# INSIDER.net
KiCad netlist of a schematic drawn in EAGLE
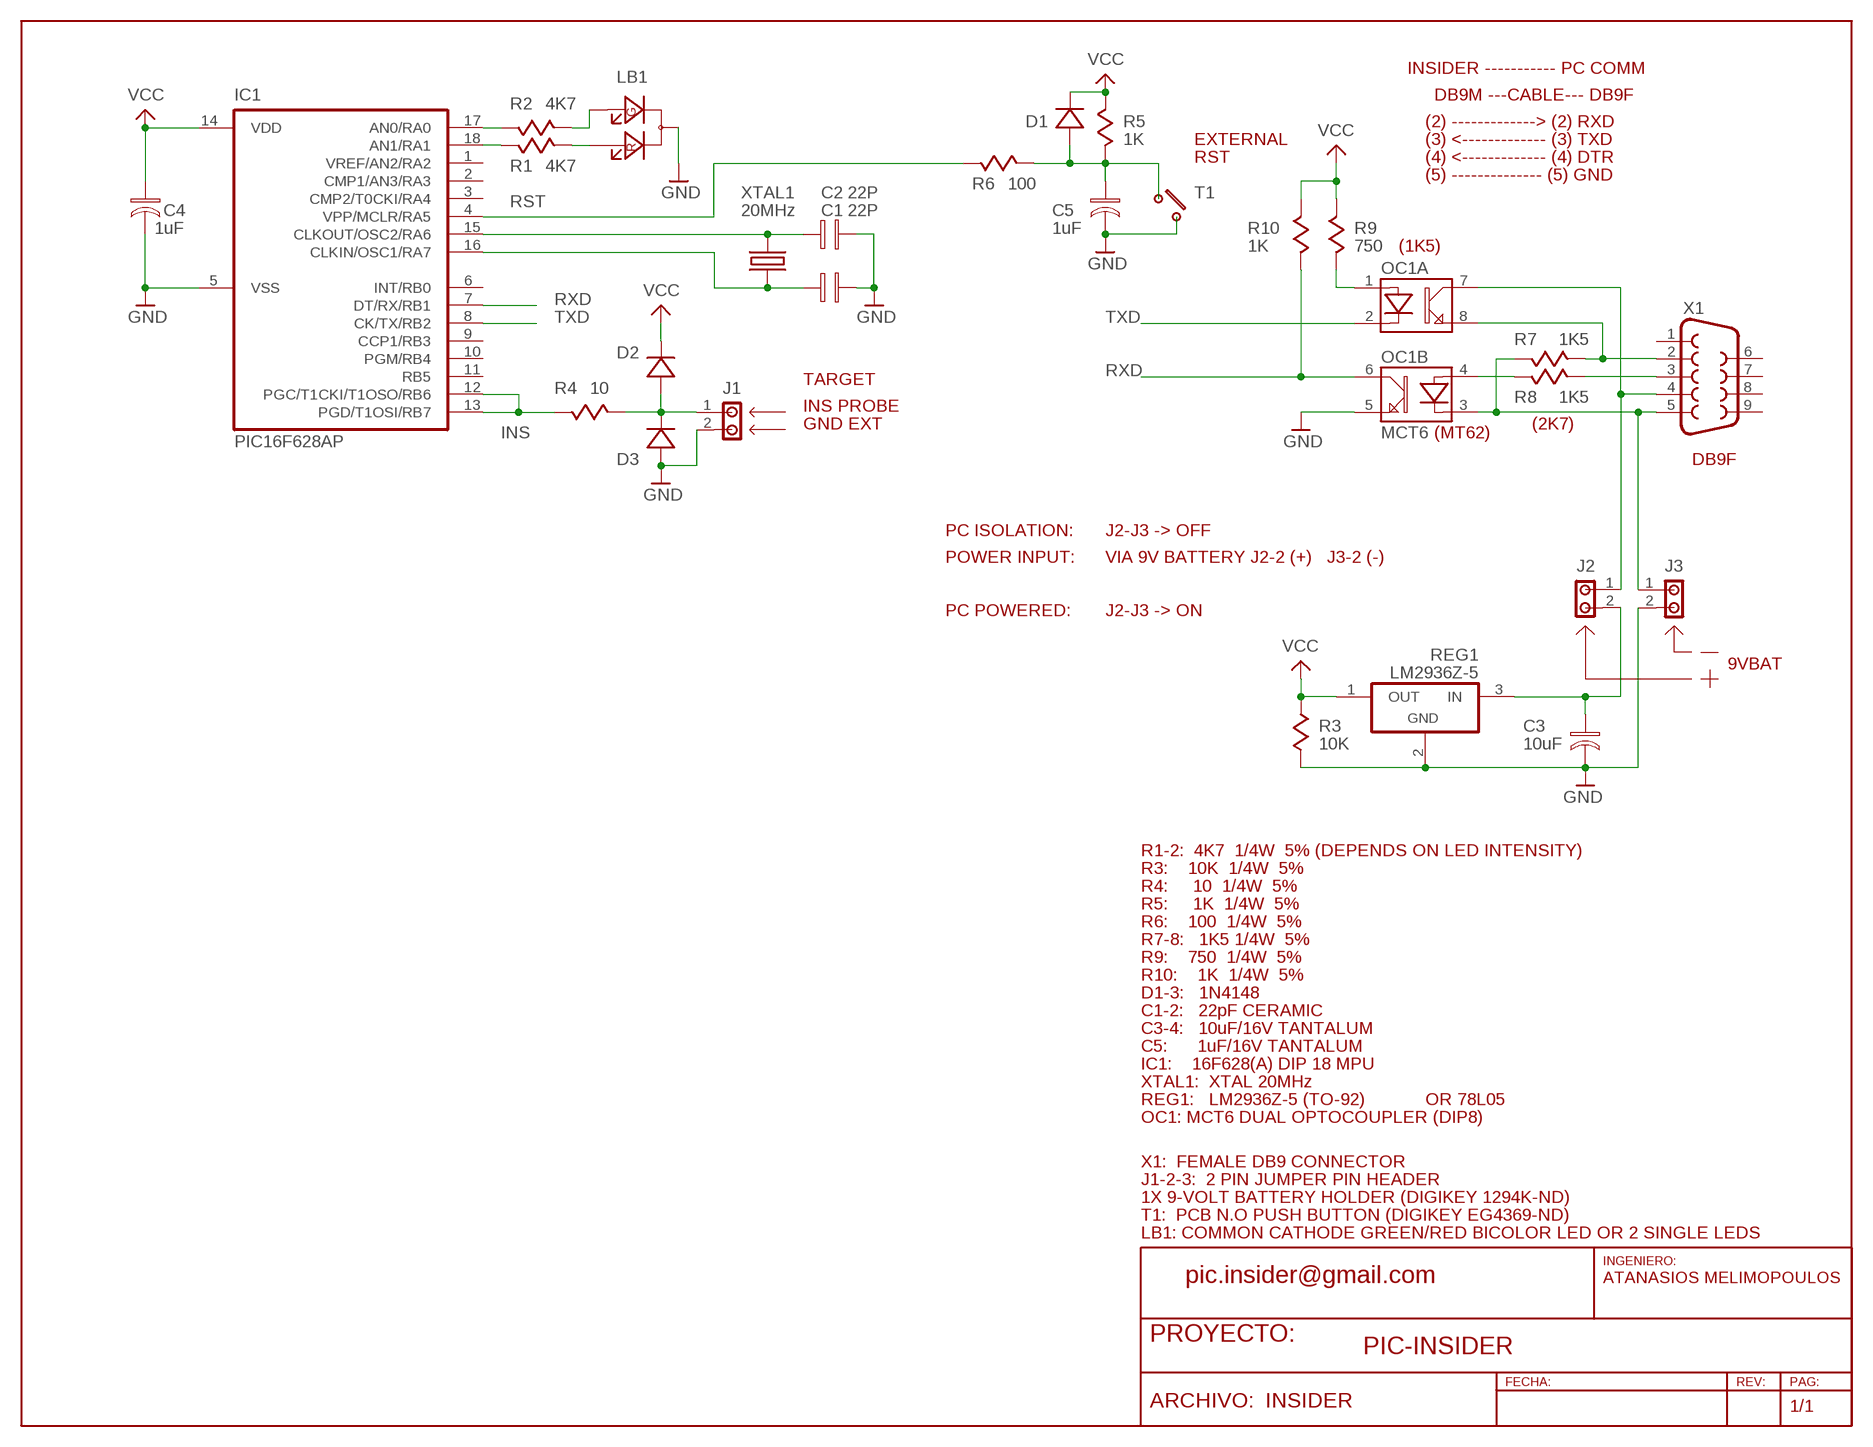
[diagram p0: schematic, sheet 1]

(export (version "E")
  (design (tool "Eeschema 10.0.6"))
  (components
    (comp (ref "C1")
      (value "22P")
      (footprint "eagle-import:C02")
      (libsource (lib "eagle-import") (part "CAP02"))
    )
    (comp (ref "C2")
      (value "22P")
      (footprint "eagle-import:C02")
      (libsource (lib "eagle-import") (part "CAP02"))
    )
    (comp (ref "C3")
      (value "10uF")
      (footprint "eagle-import:CP01")
      (libsource (lib "eagle-import") (part "CAPE01"))
    )
    (comp (ref "C4")
      (value "1uF")
      (footprint "eagle-import:CP01")
      (libsource (lib "eagle-import") (part "CAPE01"))
    )
    (comp (ref "C5")
      (value "1uF")
      (footprint "eagle-import:CP01")
      (libsource (lib "eagle-import") (part "CAPE01"))
    )
    (comp (ref "D1")
      (value "1N4148")
      (footprint "eagle-import:D03")
      (libsource (lib "eagle-import") (part "DIODE03"))
    )
    (comp (ref "D2")
      (value "1N4148")
      (footprint "eagle-import:D03")
      (libsource (lib "eagle-import") (part "DIODE03"))
    )
    (comp (ref "D3")
      (value "1N4148")
      (footprint "eagle-import:D03")
      (libsource (lib "eagle-import") (part "DIODE03"))
    )
    (comp (ref "IC1")
      (value "PIC16F628AP")
      (footprint "eagle-import:DIL18")
      (libsource (lib "eagle-import") (part "PIC16F6P28A"))
    )
    (comp (ref "J1")
      (value "JMP2")
      (footprint "eagle-import:JP2")
      (libsource (lib "eagle-import") (part "JMP2"))
    )
    (comp (ref "J2")
      (value "JMP2")
      (footprint "eagle-import:JP2")
      (libsource (lib "eagle-import") (part "JMP2"))
    )
    (comp (ref "J3")
      (value "JMP2")
      (footprint "eagle-import:JP2")
      (libsource (lib "eagle-import") (part "JMP2"))
    )
    (comp (ref "LB1")
      (value "LEDBIKC")
      (footprint "eagle-import:LEDBKC")
      (libsource (lib "eagle-import") (part "LEDBIKC"))
    )
    (comp (ref "OC1")
      (value "MCT6")
      (footprint "eagle-import:DIL08")
      (libsource (lib "eagle-import") (part "OPTO2G"))
    )
    (comp (ref "R1")
      (value "4K7")
      (footprint "eagle-import:R03")
      (libsource (lib "eagle-import") (part "RES03"))
    )
    (comp (ref "R2")
      (value "4K7")
      (footprint "eagle-import:R03")
      (libsource (lib "eagle-import") (part "RES03"))
    )
    (comp (ref "R3")
      (value "10K")
      (footprint "eagle-import:R03")
      (libsource (lib "eagle-import") (part "RES03"))
    )
    (comp (ref "R4")
      (value "10")
      (footprint "eagle-import:R03")
      (libsource (lib "eagle-import") (part "RES03"))
    )
    (comp (ref "R5")
      (value "1K")
      (footprint "eagle-import:R03")
      (libsource (lib "eagle-import") (part "RES03"))
    )
    (comp (ref "R6")
      (value "100")
      (footprint "eagle-import:R03")
      (libsource (lib "eagle-import") (part "RES03"))
    )
    (comp (ref "R7")
      (value "1K5")
      (footprint "eagle-import:R03")
      (libsource (lib "eagle-import") (part "RES03"))
    )
    (comp (ref "R8")
      (value "1K5")
      (footprint "eagle-import:R03")
      (libsource (lib "eagle-import") (part "RES03"))
    )
    (comp (ref "R9")
      (value "750")
      (footprint "eagle-import:R03")
      (libsource (lib "eagle-import") (part "RES03"))
    )
    (comp (ref "R10")
      (value "1K")
      (footprint "eagle-import:R03")
      (libsource (lib "eagle-import") (part "RES03"))
    )
    (comp (ref "REG1")
      (value "LM2936Z-5")
      (footprint "eagle-import:TO92A")
      (libsource (lib "eagle-import") (part "78XXL"))
    )
    (comp (ref "T1")
      (value "TEC3")
      (footprint "eagle-import:TEC3L")
      (libsource (lib "eagle-import") (part "TEC3"))
    )
    (comp (ref "X1")
      (value "F09D")
      (footprint "eagle-import:F09D")
      (libsource (lib "eagle-import") (part "F09D"))
    )
    (comp (ref "XTAL1")
      (value "20MHz")
      (footprint "eagle-import:HC49V")
      (libsource (lib "eagle-import") (part "XTALV300"))
    )
  )
  (nets
    (net (code "1") (name "/INS") (class "Default")
      (node (ref "IC1") (pin "12") (pinfunction "PGC/T1CKI/T1OSO/RB6_12") (pintype "bidirectional"))
      (node (ref "IC1") (pin "13") (pinfunction "PGD/T1OSI/RB7_13") (pintype "bidirectional"))
      (node (ref "R4") (pin "P$1") (pinfunction "1_P$1") (pintype "passive"))
    )
    (net (code "2") (name "/RST") (class "Default")
      (node (ref "IC1") (pin "4") (pinfunction "VPP/MCLR/RA5_4") (pintype "input"))
      (node (ref "R6") (pin "P$1") (pinfunction "1_P$1") (pintype "passive"))
    )
    (net (code "3") (name "/RXD") (class "Default")
      (node (ref "IC1") (pin "7") (pinfunction "DT/RX/RB1_7") (pintype "bidirectional"))
      (node (ref "OC1") (pin "6") (pinfunction "C_6") (pintype "passive"))
      (node (ref "R10") (pin "P$1") (pinfunction "1_P$1") (pintype "passive"))
    )
    (net (code "4") (name "/TXD") (class "Default")
      (node (ref "IC1") (pin "8") (pinfunction "CK/TX/RB2_8") (pintype "bidirectional"))
      (node (ref "OC1") (pin "2") (pinfunction "K_2") (pintype "passive"))
    )
    (net (code "5") (name "GND") (class "Default")
      (node (ref "C1") (pin "P$2") (pinfunction "2_P$2") (pintype "passive"))
      (node (ref "C2") (pin "P$2") (pinfunction "2_P$2") (pintype "passive"))
      (node (ref "C3") (pin "P$2") (pinfunction "2_P$2") (pintype "passive"))
      (node (ref "C4") (pin "P$2") (pinfunction "2_P$2") (pintype "passive"))
      (node (ref "C5") (pin "P$2") (pinfunction "2_P$2") (pintype "passive"))
      (node (ref "D3") (pin "P$1") (pinfunction "A_P$1") (pintype "passive"))
      (node (ref "IC1") (pin "5") (pinfunction "VSS_5") (pintype "power_in"))
      (node (ref "J1") (pin "2") (pinfunction "P$2_2") (pintype "bidirectional"))
      (node (ref "J3") (pin "2") (pinfunction "P$2_2") (pintype "bidirectional"))
      (node (ref "LB1") (pin "K") (pinfunction "K_K") (pintype "passive"))
      (node (ref "OC1") (pin "5") (pinfunction "E_5") (pintype "passive"))
      (node (ref "R3") (pin "P$2") (pinfunction "2_P$2") (pintype "passive"))
      (node (ref "REG1") (pin "2") (pinfunction "GND_2") (pintype "input"))
      (node (ref "T1") (pin "4") (pinfunction "P$2_4") (pintype "passive"))
    )
    (net (code "6") (name "Net-(C1-1)") (class "Default")
      (node (ref "C1") (pin "P$1") (pinfunction "1_P$1") (pintype "passive"))
      (node (ref "IC1") (pin "16") (pinfunction "CLKIN/OSC1/RA7_16") (pintype "bidirectional"))
      (node (ref "XTAL1") (pin "2") (pinfunction "P$2_2") (pintype "passive"))
    )
    (net (code "7") (name "Net-(C2-1)") (class "Default")
      (node (ref "C2") (pin "P$1") (pinfunction "1_P$1") (pintype "passive"))
      (node (ref "IC1") (pin "15") (pinfunction "CLKOUT/OSC2/RA6_15") (pintype "bidirectional"))
      (node (ref "XTAL1") (pin "1") (pinfunction "P$1_1") (pintype "passive"))
    )
    (net (code "8") (name "Net-(C3-1)") (class "Default")
      (node (ref "C3") (pin "P$1") (pinfunction "1_P$1") (pintype "passive"))
      (node (ref "J2") (pin "2") (pinfunction "P$2_2") (pintype "bidirectional"))
      (node (ref "REG1") (pin "3") (pinfunction "IN_3") (pintype "input"))
    )
    (net (code "9") (name "Net-(C5-1)") (class "Default")
      (node (ref "C5") (pin "P$1") (pinfunction "1_P$1") (pintype "passive"))
      (node (ref "D1") (pin "P$1") (pinfunction "A_P$1") (pintype "passive"))
      (node (ref "R5") (pin "P$2") (pinfunction "2_P$2") (pintype "passive"))
      (node (ref "R6") (pin "P$2") (pinfunction "2_P$2") (pintype "passive"))
      (node (ref "T1") (pin "1") (pinfunction "P$1_1") (pintype "passive"))
    )
    (net (code "10") (name "Net-(D2-A)") (class "Default")
      (node (ref "D2") (pin "P$1") (pinfunction "A_P$1") (pintype "passive"))
      (node (ref "D3") (pin "P$2") (pinfunction "K_P$2") (pintype "passive"))
      (node (ref "J1") (pin "1") (pinfunction "P$1_1") (pintype "bidirectional"))
      (node (ref "R4") (pin "P$2") (pinfunction "2_P$2") (pintype "passive"))
    )
    (net (code "11") (name "Net-(IC1-AN0{slash}RA0)") (class "Default")
      (node (ref "IC1") (pin "17") (pinfunction "AN0/RA0_17") (pintype "bidirectional"))
      (node (ref "R2") (pin "P$2") (pinfunction "2_P$2") (pintype "passive"))
    )
    (net (code "12") (name "Net-(IC1-AN1{slash}RA1)") (class "Default")
      (node (ref "IC1") (pin "18") (pinfunction "AN1/RA1_18") (pintype "bidirectional"))
      (node (ref "R1") (pin "P$2") (pinfunction "2_P$2") (pintype "passive"))
    )
    (net (code "13") (name "Net-(J2-P$1)") (class "Default")
      (node (ref "J2") (pin "1") (pinfunction "P$1_1") (pintype "bidirectional"))
      (node (ref "OC1") (pin "7") (pinfunction "C_7") (pintype "passive"))
      (node (ref "X1") (pin "4") (pinfunction "4_4") (pintype "passive"))
    )
    (net (code "14") (name "Net-(J3-P$1)") (class "Default")
      (node (ref "J3") (pin "1") (pinfunction "P$1_1") (pintype "bidirectional"))
      (node (ref "OC1") (pin "3") (pinfunction "K_3") (pintype "passive"))
      (node (ref "R7") (pin "P$2") (pinfunction "2_P$2") (pintype "passive"))
      (node (ref "X1") (pin "5") (pinfunction "5_5") (pintype "passive"))
    )
    (net (code "15") (name "Net-(LB1-A1)") (class "Default")
      (node (ref "LB1") (pin "R") (pinfunction "A1_R") (pintype "passive"))
      (node (ref "R1") (pin "P$1") (pinfunction "1_P$1") (pintype "passive"))
    )
    (net (code "16") (name "Net-(LB1-A2)") (class "Default")
      (node (ref "LB1") (pin "G") (pinfunction "A2_G") (pintype "passive"))
      (node (ref "R2") (pin "P$1") (pinfunction "1_P$1") (pintype "passive"))
    )
    (net (code "17") (name "Net-(OC1A-A)") (class "Default")
      (node (ref "OC1") (pin "1") (pinfunction "A_1") (pintype "passive"))
      (node (ref "R9") (pin "P$1") (pinfunction "1_P$1") (pintype "passive"))
    )
    (net (code "18") (name "Net-(OC1A-E)") (class "Default")
      (node (ref "OC1") (pin "8") (pinfunction "E_8") (pintype "passive"))
      (node (ref "R7") (pin "P$1") (pinfunction "1_P$1") (pintype "passive"))
      (node (ref "X1") (pin "2") (pinfunction "2_2") (pintype "passive"))
    )
    (net (code "19") (name "Net-(OC1B-A)") (class "Default")
      (node (ref "OC1") (pin "4") (pinfunction "A_4") (pintype "passive"))
      (node (ref "R8") (pin "P$2") (pinfunction "2_P$2") (pintype "passive"))
    )
    (net (code "20") (name "Net-(R8-1)") (class "Default")
      (node (ref "R8") (pin "P$1") (pinfunction "1_P$1") (pintype "passive"))
      (node (ref "X1") (pin "3") (pinfunction "3_3") (pintype "passive"))
    )
    (net (code "21") (name "VCC") (class "Default")
      (node (ref "C4") (pin "P$1") (pinfunction "1_P$1") (pintype "passive"))
      (node (ref "D1") (pin "P$2") (pinfunction "K_P$2") (pintype "passive"))
      (node (ref "D2") (pin "P$2") (pinfunction "K_P$2") (pintype "passive"))
      (node (ref "IC1") (pin "14") (pinfunction "VDD_14") (pintype "power_in"))
      (node (ref "R10") (pin "P$2") (pinfunction "2_P$2") (pintype "passive"))
      (node (ref "R3") (pin "P$1") (pinfunction "1_P$1") (pintype "passive"))
      (node (ref "R5") (pin "P$1") (pinfunction "1_P$1") (pintype "passive"))
      (node (ref "R9") (pin "P$2") (pinfunction "2_P$2") (pintype "passive"))
      (node (ref "REG1") (pin "1") (pinfunction "OUT_1") (pintype "passive"))
    )
    (net (code "22") (name "unconnected-(IC1-CCP1{slash}RB3-Pad9)") (class "Default")
      (node (ref "IC1") (pin "9") (pinfunction "CCP1/RB3_9") (pintype "bidirectional"))
    )
    (net (code "23") (name "unconnected-(IC1-CMP1{slash}AN3{slash}RA3-Pad2)") (class "Default")
      (node (ref "IC1") (pin "2") (pinfunction "CMP1/AN3/RA3_2") (pintype "bidirectional"))
    )
    (net (code "24") (name "unconnected-(IC1-CMP2{slash}T0CKI{slash}RA4-Pad3)") (class "Default")
      (node (ref "IC1") (pin "3") (pinfunction "CMP2/T0CKI/RA4_3") (pintype "bidirectional"))
    )
    (net (code "25") (name "unconnected-(IC1-INT{slash}RB0-Pad6)") (class "Default")
      (node (ref "IC1") (pin "6") (pinfunction "INT/RB0_6") (pintype "bidirectional"))
    )
    (net (code "26") (name "unconnected-(IC1-PGM{slash}RB4-Pad10)") (class "Default")
      (node (ref "IC1") (pin "10") (pinfunction "PGM/RB4_10") (pintype "bidirectional"))
    )
    (net (code "27") (name "unconnected-(IC1-RB5-Pad11)") (class "Default")
      (node (ref "IC1") (pin "11") (pinfunction "RB5_11") (pintype "bidirectional"))
    )
    (net (code "28") (name "unconnected-(IC1-VREF{slash}AN2{slash}RA2-Pad1)") (class "Default")
      (node (ref "IC1") (pin "1") (pinfunction "VREF/AN2/RA2_1") (pintype "bidirectional"))
    )
    (net (code "29") (name "unconnected-(X1-Pad1)") (class "Default")
      (node (ref "X1") (pin "1") (pinfunction "1_1") (pintype "passive"))
    )
    (net (code "30") (name "unconnected-(X1-Pad6)") (class "Default")
      (node (ref "X1") (pin "6") (pinfunction "6_6") (pintype "passive"))
    )
    (net (code "31") (name "unconnected-(X1-Pad7)") (class "Default")
      (node (ref "X1") (pin "7") (pinfunction "7_7") (pintype "passive"))
    )
    (net (code "32") (name "unconnected-(X1-Pad8)") (class "Default")
      (node (ref "X1") (pin "8") (pinfunction "8_8") (pintype "passive"))
    )
    (net (code "33") (name "unconnected-(X1-Pad9)") (class "Default")
      (node (ref "X1") (pin "9") (pinfunction "9_9") (pintype "passive"))
    )
  )
)
